# rc-driver-dual.net
KiCad netlist of a schematic drawn in EAGLE
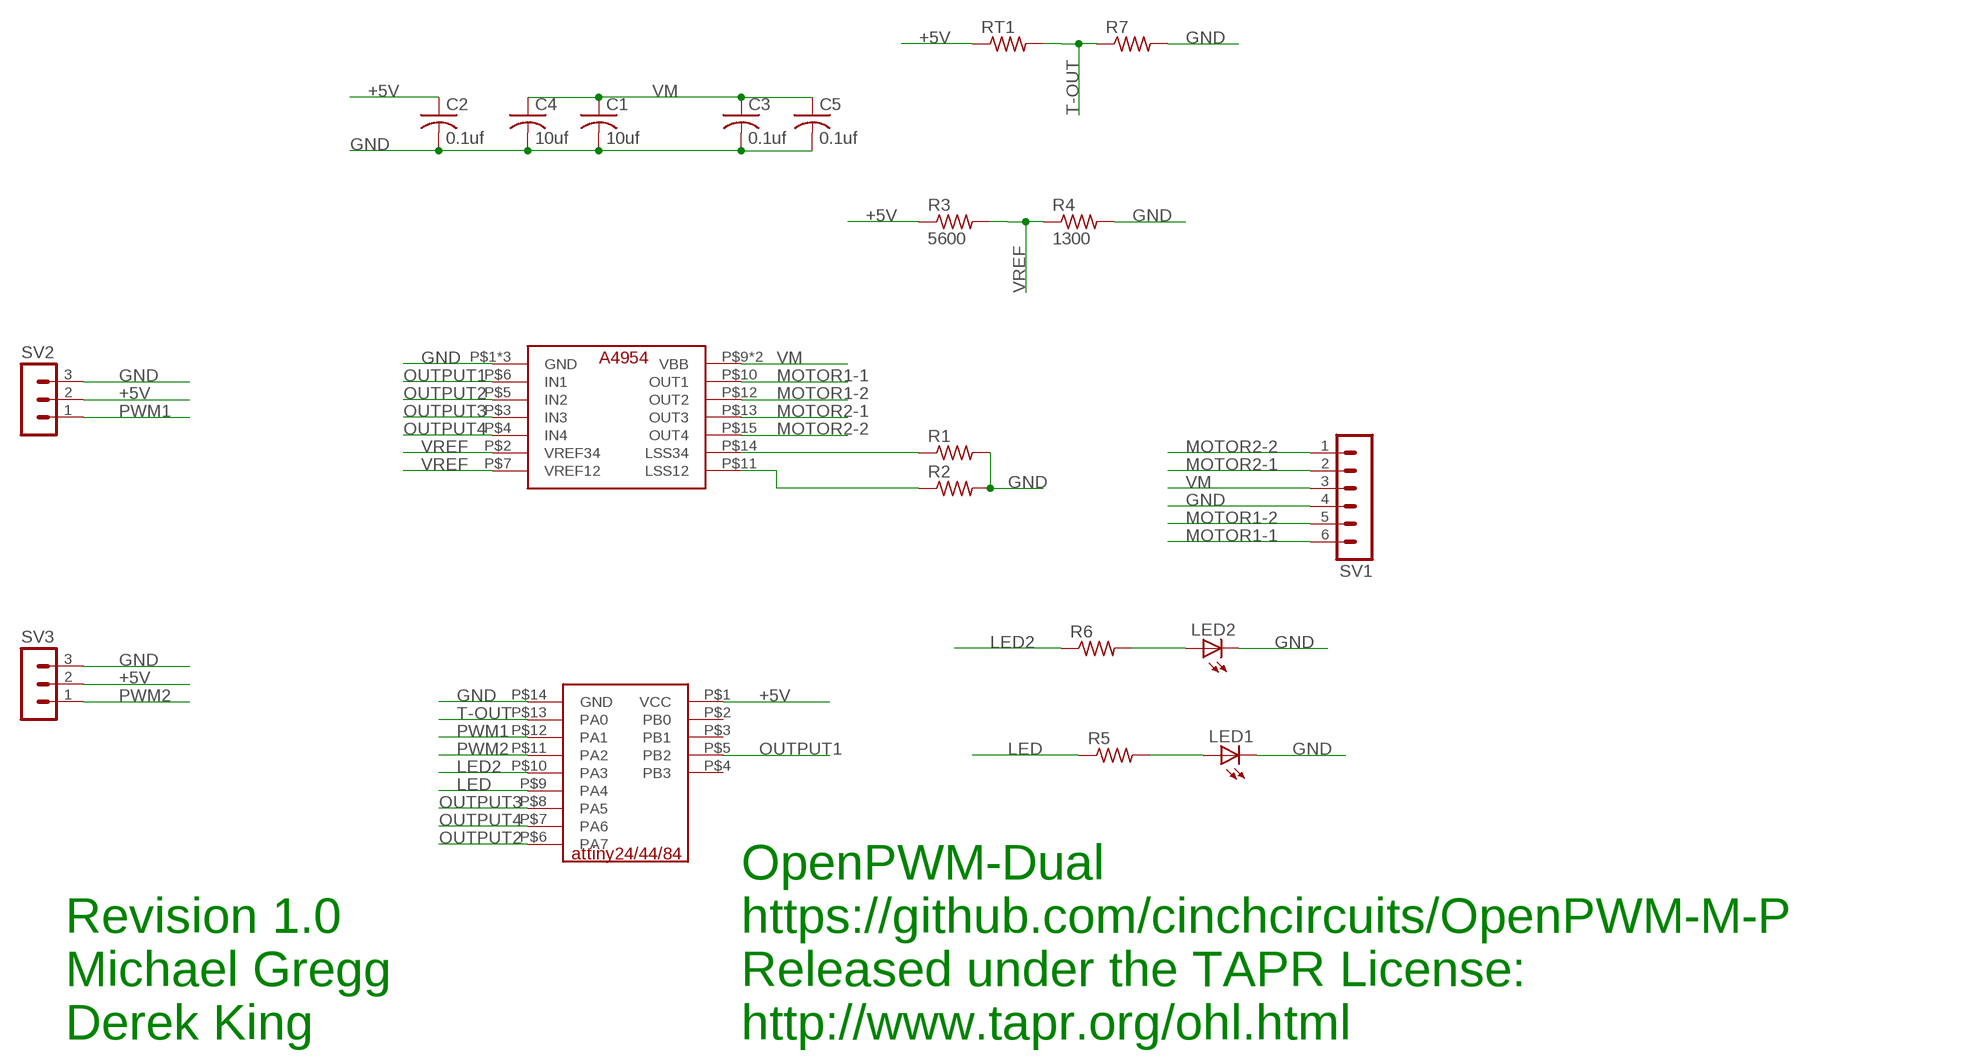
[diagram p0: schematic, sheet 1]

(export (version "E")
  (design (tool "Eeschema 10.0.6"))
  (components
    (comp (ref "C1")
      (value "10uf")
      (footprint "eagle-import:C1206")
      (libsource (lib "eagle-import") (part "C-USC1206"))
    )
    (comp (ref "C2")
      (value "0.1uf")
      (footprint "eagle-import:C0603")
      (libsource (lib "eagle-import") (part "C-USC0603"))
    )
    (comp (ref "C3")
      (value "0.1uf")
      (footprint "eagle-import:C0603")
      (libsource (lib "eagle-import") (part "C-USC0603"))
    )
    (comp (ref "C4")
      (value "10uf")
      (footprint "eagle-import:C1206")
      (libsource (lib "eagle-import") (part "C-USC1206"))
    )
    (comp (ref "C5")
      (value "0.1uf")
      (footprint "eagle-import:C0603")
      (libsource (lib "eagle-import") (part "C-USC0603"))
    )
    (comp (ref "LED1")
      (value "LEDCHIPLED_0603")
      (footprint "eagle-import:CHIPLED_0603")
      (libsource (lib "eagle-import") (part "LEDCHIPLED_0603"))
    )
    (comp (ref "LED2")
      (value "LEDCHIPLED_0603")
      (footprint "eagle-import:CHIPLED_0603")
      (libsource (lib "eagle-import") (part "LEDCHIPLED_0603"))
    )
    (comp (ref "R1")
      (value "R-US_R0805W")
      (footprint "eagle-import:R0805W")
      (libsource (lib "eagle-import") (part "R-US_R0805W"))
    )
    (comp (ref "R2")
      (value "R-US_R0805W")
      (footprint "eagle-import:R0805W")
      (libsource (lib "eagle-import") (part "R-US_R0805W"))
    )
    (comp (ref "R3")
      (value "5600")
      (footprint "eagle-import:R0603")
      (libsource (lib "eagle-import") (part "R-US_R0603"))
    )
    (comp (ref "R4")
      (value "1300")
      (footprint "eagle-import:R0603")
      (libsource (lib "eagle-import") (part "R-US_R0603"))
    )
    (comp (ref "R5")
      (value "R-US_R0603")
      (footprint "eagle-import:R0603")
      (libsource (lib "eagle-import") (part "R-US_R0603"))
    )
    (comp (ref "R6")
      (value "R-US_R0603")
      (footprint "eagle-import:R0603")
      (libsource (lib "eagle-import") (part "R-US_R0603"))
    )
    (comp (ref "R7")
      (value "R-US_R0603")
      (footprint "eagle-import:R0603")
      (libsource (lib "eagle-import") (part "R-US_R0603"))
    )
    (comp (ref "RT1")
      (value "R-US_R0603")
      (footprint "eagle-import:R0603")
      (libsource (lib "eagle-import") (part "R-US_R0603"))
    )
    (comp (ref "SV1")
      (value "MA06-1")
      (footprint "eagle-import:MA06-1")
      (libsource (lib "eagle-import") (part "MA06-1"))
    )
    (comp (ref "SV2")
      (value "MA03-1")
      (footprint "eagle-import:MA03-1")
      (libsource (lib "eagle-import") (part "MA03-1"))
    )
    (comp (ref "SV3")
      (value "MA03-1")
      (footprint "eagle-import:MA03-1")
      (libsource (lib "eagle-import") (part "MA03-1"))
    )
    (comp (ref "U$1")
      (value "ATTINY24A")
      (footprint "eagle-import:SOIC-14-WIDE")
      (libsource (lib "eagle-import") (part "ATTINY24A"))
    )
    (comp (ref "U$2")
      (value "A4954-DUAL-HBRIDGE")
      (footprint "eagle-import:TSSOP-16-LP")
      (libsource (lib "eagle-import") (part "A4954-DUAL-HBRIDGE"))
    )
  )
  (nets
    (net (code "1") (name "/+5V") (class "Default")
      (node (ref "C2") (pin "1") (pinfunction "1_1") (pintype "passive"))
      (node (ref "R3") (pin "1") (pinfunction "1_1") (pintype "passive"))
      (node (ref "RT1") (pin "1") (pinfunction "1_1") (pintype "passive"))
      (node (ref "SV2") (pin "2") (pinfunction "2_2") (pintype "passive"))
      (node (ref "SV3") (pin "2") (pinfunction "2_2") (pintype "passive"))
      (node (ref "U$1") (pin "P$1") (pinfunction "VCC_P$1") (pintype "bidirectional"))
    )
    (net (code "2") (name "/GND") (class "Default")
      (node (ref "C1") (pin "2") (pinfunction "2_2") (pintype "passive"))
      (node (ref "C2") (pin "2") (pinfunction "2_2") (pintype "passive"))
      (node (ref "C3") (pin "2") (pinfunction "2_2") (pintype "passive"))
      (node (ref "C4") (pin "2") (pinfunction "2_2") (pintype "passive"))
      (node (ref "C5") (pin "2") (pinfunction "2_2") (pintype "passive"))
      (node (ref "LED1") (pin "C") (pinfunction "C_C") (pintype "passive"))
      (node (ref "LED2") (pin "C") (pinfunction "C_C") (pintype "passive"))
      (node (ref "R1") (pin "2") (pinfunction "2_2") (pintype "passive"))
      (node (ref "R2") (pin "2") (pinfunction "2_2") (pintype "passive"))
      (node (ref "R4") (pin "2") (pinfunction "2_2") (pintype "passive"))
      (node (ref "R7") (pin "2") (pinfunction "2_2") (pintype "passive"))
      (node (ref "SV1") (pin "4") (pinfunction "4_4") (pintype "passive"))
      (node (ref "SV2") (pin "3") (pinfunction "3_3") (pintype "passive"))
      (node (ref "SV3") (pin "3") (pinfunction "3_3") (pintype "passive"))
      (node (ref "U$1") (pin "P$14") (pinfunction "GND_P$14") (pintype "bidirectional"))
      (node (ref "U$2") (pin "P$1") (pinfunction "GND_P$1") (pintype "bidirectional"))
      (node (ref "U$2") (pin "P$17") (pinfunction "GND_P$17") (pintype "bidirectional"))
      (node (ref "U$2") (pin "P$8") (pinfunction "GND_P$8") (pintype "bidirectional"))
    )
    (net (code "3") (name "/LED") (class "Default")
      (node (ref "R5") (pin "1") (pinfunction "1_1") (pintype "passive"))
      (node (ref "U$1") (pin "P$9") (pinfunction "PA4_P$9") (pintype "bidirectional"))
    )
    (net (code "4") (name "/LED2") (class "Default")
      (node (ref "R6") (pin "1") (pinfunction "1_1") (pintype "passive"))
      (node (ref "U$1") (pin "P$10") (pinfunction "PA3_P$10") (pintype "bidirectional"))
    )
    (net (code "5") (name "/MOTOR1-1") (class "Default")
      (node (ref "SV1") (pin "6") (pinfunction "6_6") (pintype "passive"))
      (node (ref "U$2") (pin "P$10") (pinfunction "OUT1_P$10") (pintype "bidirectional"))
    )
    (net (code "6") (name "/MOTOR1-2") (class "Default")
      (node (ref "SV1") (pin "5") (pinfunction "5_5") (pintype "passive"))
      (node (ref "U$2") (pin "P$12") (pinfunction "OUT2_P$12") (pintype "bidirectional"))
    )
    (net (code "7") (name "/MOTOR2-1") (class "Default")
      (node (ref "SV1") (pin "2") (pinfunction "2_2") (pintype "passive"))
      (node (ref "U$2") (pin "P$13") (pinfunction "OUT3_P$13") (pintype "bidirectional"))
    )
    (net (code "8") (name "/MOTOR2-2") (class "Default")
      (node (ref "SV1") (pin "1") (pinfunction "1_1") (pintype "passive"))
      (node (ref "U$2") (pin "P$15") (pinfunction "OUT4_P$15") (pintype "bidirectional"))
    )
    (net (code "9") (name "/OUTPUT1") (class "Default")
      (node (ref "U$1") (pin "P$5") (pinfunction "PB2_P$5") (pintype "bidirectional"))
      (node (ref "U$2") (pin "P$6") (pinfunction "IN1_P$6") (pintype "bidirectional"))
    )
    (net (code "10") (name "/OUTPUT2") (class "Default")
      (node (ref "U$1") (pin "P$6") (pinfunction "PA7_P$6") (pintype "bidirectional"))
      (node (ref "U$2") (pin "P$5") (pinfunction "IN2_P$5") (pintype "bidirectional"))
    )
    (net (code "11") (name "/OUTPUT3") (class "Default")
      (node (ref "U$1") (pin "P$8") (pinfunction "PA5_P$8") (pintype "bidirectional"))
      (node (ref "U$2") (pin "P$3") (pinfunction "IN3_P$3") (pintype "bidirectional"))
    )
    (net (code "12") (name "/OUTPUT4") (class "Default")
      (node (ref "U$1") (pin "P$7") (pinfunction "PA6_P$7") (pintype "bidirectional"))
      (node (ref "U$2") (pin "P$4") (pinfunction "IN4_P$4") (pintype "bidirectional"))
    )
    (net (code "13") (name "/PWM1") (class "Default")
      (node (ref "SV2") (pin "1") (pinfunction "1_1") (pintype "passive"))
      (node (ref "U$1") (pin "P$12") (pinfunction "PA1_P$12") (pintype "bidirectional"))
    )
    (net (code "14") (name "/PWM2") (class "Default")
      (node (ref "SV3") (pin "1") (pinfunction "1_1") (pintype "passive"))
      (node (ref "U$1") (pin "P$11") (pinfunction "PA2_P$11") (pintype "bidirectional"))
    )
    (net (code "15") (name "/T-OUT") (class "Default")
      (node (ref "R7") (pin "1") (pinfunction "1_1") (pintype "passive"))
      (node (ref "RT1") (pin "2") (pinfunction "2_2") (pintype "passive"))
      (node (ref "U$1") (pin "P$13") (pinfunction "PA0_P$13") (pintype "bidirectional"))
    )
    (net (code "16") (name "/VM") (class "Default")
      (node (ref "C1") (pin "1") (pinfunction "1_1") (pintype "passive"))
      (node (ref "C3") (pin "1") (pinfunction "1_1") (pintype "passive"))
      (node (ref "C4") (pin "1") (pinfunction "1_1") (pintype "passive"))
      (node (ref "C5") (pin "1") (pinfunction "1_1") (pintype "passive"))
      (node (ref "SV1") (pin "3") (pinfunction "3_3") (pintype "passive"))
      (node (ref "U$2") (pin "P$16") (pinfunction "VBB_P$16") (pintype "bidirectional"))
      (node (ref "U$2") (pin "P$9") (pinfunction "VBB_P$9") (pintype "bidirectional"))
    )
    (net (code "17") (name "/VREF") (class "Default")
      (node (ref "R3") (pin "2") (pinfunction "2_2") (pintype "passive"))
      (node (ref "R4") (pin "1") (pinfunction "1_1") (pintype "passive"))
      (node (ref "U$2") (pin "P$2") (pinfunction "VREF34_P$2") (pintype "bidirectional"))
      (node (ref "U$2") (pin "P$7") (pinfunction "VREF12_P$7") (pintype "bidirectional"))
    )
    (net (code "18") (name "Net-(LED1-PadA)") (class "Default")
      (node (ref "LED1") (pin "A") (pinfunction "A_A") (pintype "passive"))
      (node (ref "R5") (pin "2") (pinfunction "2_2") (pintype "passive"))
    )
    (net (code "19") (name "Net-(LED2-PadA)") (class "Default")
      (node (ref "LED2") (pin "A") (pinfunction "A_A") (pintype "passive"))
      (node (ref "R6") (pin "2") (pinfunction "2_2") (pintype "passive"))
    )
    (net (code "20") (name "Net-(U$2-LSS12)") (class "Default")
      (node (ref "R2") (pin "1") (pinfunction "1_1") (pintype "passive"))
      (node (ref "U$2") (pin "P$11") (pinfunction "LSS12_P$11") (pintype "bidirectional"))
    )
    (net (code "21") (name "Net-(U$2-LSS34)") (class "Default")
      (node (ref "R1") (pin "1") (pinfunction "1_1") (pintype "passive"))
      (node (ref "U$2") (pin "P$14") (pinfunction "LSS34_P$14") (pintype "bidirectional"))
    )
    (net (code "22") (name "unconnected-(U$1-PB0-PadP$2)") (class "Default")
      (node (ref "U$1") (pin "P$2") (pinfunction "PB0_P$2") (pintype "bidirectional"))
    )
    (net (code "23") (name "unconnected-(U$1-PB1-PadP$3)") (class "Default")
      (node (ref "U$1") (pin "P$3") (pinfunction "PB1_P$3") (pintype "bidirectional"))
    )
    (net (code "24") (name "unconnected-(U$1-PB3-PadP$4)") (class "Default")
      (node (ref "U$1") (pin "P$4") (pinfunction "PB3_P$4") (pintype "bidirectional"))
    )
  )
)
